# Modem.net
KiCad netlist of a schematic drawn in EAGLE
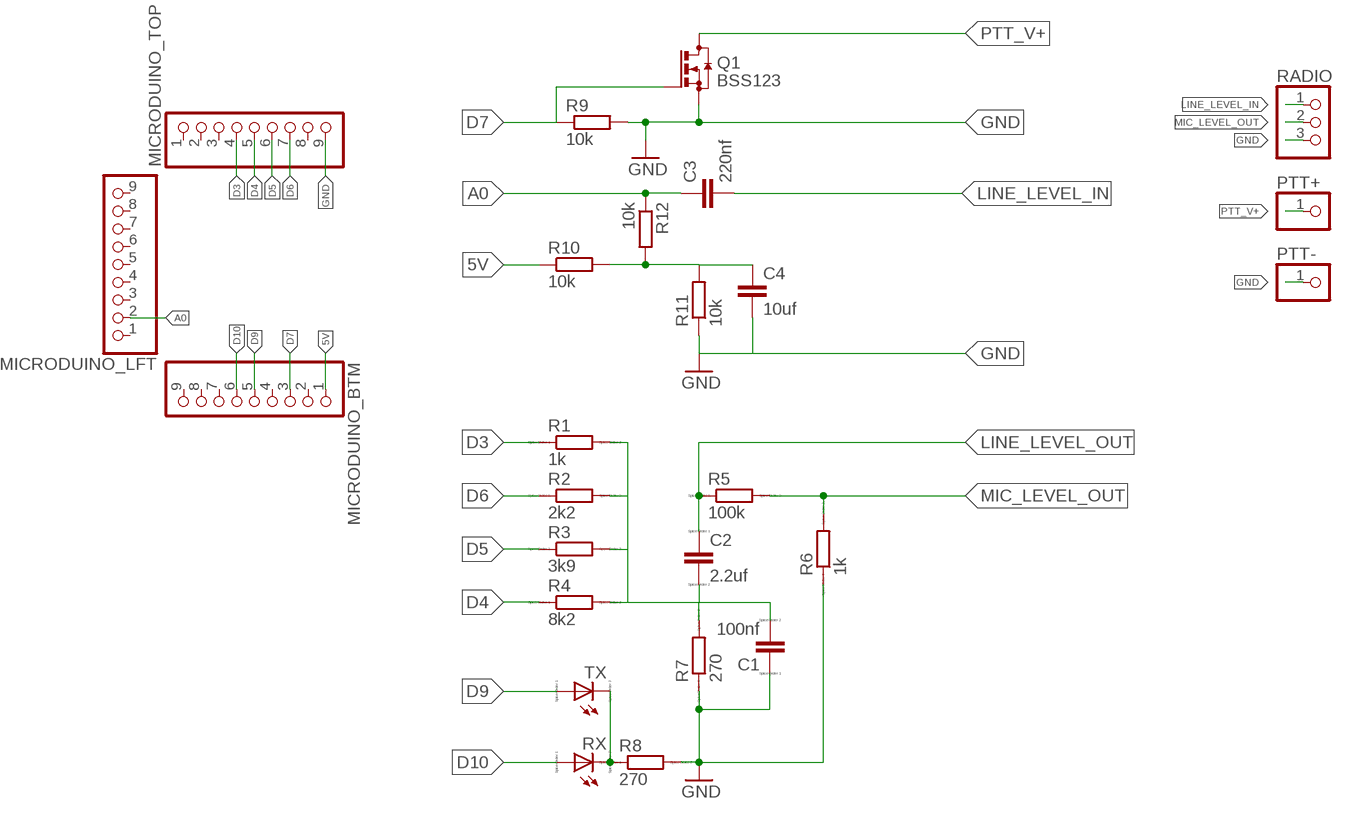
[diagram p0: schematic, sheet 1]

(export (version "E")
  (design (tool "Eeschema 10.0.6"))
  (components
    (comp (ref "C1")
      (value "100nf")
      (footprint "eagle-import:C0603")
      (libsource (lib "eagle-import") (part "CC0603"))
    )
    (comp (ref "C2")
      (value "2.2uf")
      (footprint "eagle-import:C1206")
      (libsource (lib "eagle-import") (part "CC1206"))
    )
    (comp (ref "C3")
      (value "220nf")
      (footprint "eagle-import:C0603")
      (libsource (lib "eagle-import") (part "C-EUC0603"))
    )
    (comp (ref "C4")
      (value "10uf")
      (footprint "eagle-import:C1206")
      (libsource (lib "eagle-import") (part "C-EUC1206"))
    )
    (comp (ref "MICRODUINO_BTM")
      (value "PINHD-1X9")
      (footprint "eagle-import:1X09-BIG")
      (libsource (lib "eagle-import") (part "PINHD-1X9"))
    )
    (comp (ref "MICRODUINO_LFT")
      (value "PINHD-1X9")
      (footprint "eagle-import:1X09-BIG")
      (libsource (lib "eagle-import") (part "PINHD-1X9"))
    )
    (comp (ref "MICRODUINO_TOP")
      (value "PINHD-1X9")
      (footprint "eagle-import:1X09-BIG")
      (libsource (lib "eagle-import") (part "PINHD-1X9"))
    )
    (comp (ref "PTT+")
      (value "PINHD-1X1")
      (footprint "eagle-import:1X01")
      (libsource (lib "eagle-import") (part "PINHD-1X1"))
    )
    (comp (ref "PTT-")
      (value "PINHD-1X1")
      (footprint "eagle-import:1X01")
      (libsource (lib "eagle-import") (part "PINHD-1X1"))
    )
    (comp (ref "Q1")
      (value "BSS123")
      (footprint "eagle-import:SOT23")
      (libsource (lib "eagle-import") (part "BSS123"))
    )
    (comp (ref "R1")
      (value "1k")
      (footprint "eagle-import:R0603")
      (libsource (lib "eagle-import") (part "resistor_R-EU_R0603"))
    )
    (comp (ref "R2")
      (value "2k2")
      (footprint "eagle-import:R0603")
      (libsource (lib "eagle-import") (part "resistor_R-EU_R0603"))
    )
    (comp (ref "R3")
      (value "3k9")
      (footprint "eagle-import:R0603")
      (libsource (lib "eagle-import") (part "resistor_R-EU_R0603"))
    )
    (comp (ref "R4")
      (value "8k2")
      (footprint "eagle-import:R0603")
      (libsource (lib "eagle-import") (part "resistor_R-EU_R0603"))
    )
    (comp (ref "R5")
      (value "100k")
      (footprint "eagle-import:R0603")
      (libsource (lib "eagle-import") (part "resistor_R-EU_R0603"))
    )
    (comp (ref "R6")
      (value "1k")
      (footprint "eagle-import:R0603")
      (libsource (lib "eagle-import") (part "resistor_R-EU_R0603"))
    )
    (comp (ref "R7")
      (value "270")
      (footprint "eagle-import:R0603")
      (libsource (lib "eagle-import") (part "resistor_R-EU_R0603"))
    )
    (comp (ref "R8")
      (value "270")
      (footprint "eagle-import:R0603")
      (libsource (lib "eagle-import") (part "resistor_R-EU_R0603"))
    )
    (comp (ref "R9")
      (value "10k")
      (footprint "eagle-import:R0603")
      (libsource (lib "eagle-import") (part "R-EU_R0603"))
    )
    (comp (ref "R10")
      (value "10k")
      (footprint "eagle-import:R0603")
      (libsource (lib "eagle-import") (part "R-EU_R0603"))
    )
    (comp (ref "R11")
      (value "10k")
      (footprint "eagle-import:R0603")
      (libsource (lib "eagle-import") (part "R-EU_R0603"))
    )
    (comp (ref "R12")
      (value "10k")
      (footprint "eagle-import:R0603")
      (libsource (lib "eagle-import") (part "R-EU_R0603"))
    )
    (comp (ref "RADIO")
      (value "PINHD-1X3")
      (footprint "eagle-import:1X03")
      (libsource (lib "eagle-import") (part "PINHD-1X3"))
    )
    (comp (ref "RX")
      (value "LED_E")
      (footprint "eagle-import:LED_1206")
      (libsource (lib "eagle-import") (part "LED_E"))
    )
    (comp (ref "TX")
      (value "LED_E")
      (footprint "eagle-import:LED_1206")
      (libsource (lib "eagle-import") (part "LED_E"))
    )
  )
  (nets
    (net (code "1") (name "5V") (class "Default")
      (node (ref "MICRODUINO_BTM") (pin "1") (pinfunction "1_1") (pintype "passive"))
      (node (ref "R10") (pin "1") (pinfunction "1_1") (pintype "passive"))
    )
    (net (code "2") (name "A0") (class "Default")
      (node (ref "C3") (pin "1") (pinfunction "1_1") (pintype "passive"))
      (node (ref "MICRODUINO_LFT") (pin "2") (pinfunction "2_2") (pintype "passive"))
      (node (ref "R12") (pin "1") (pinfunction "1_1") (pintype "passive"))
    )
    (net (code "3") (name "D3") (class "Default")
      (node (ref "MICRODUINO_TOP") (pin "4") (pinfunction "4_4") (pintype "passive"))
      (node (ref "R1") (pin "1") (pinfunction "1_1") (pintype "passive"))
    )
    (net (code "4") (name "D4") (class "Default")
      (node (ref "MICRODUINO_TOP") (pin "5") (pinfunction "5_5") (pintype "passive"))
      (node (ref "R4") (pin "1") (pinfunction "1_1") (pintype "passive"))
    )
    (net (code "5") (name "D5") (class "Default")
      (node (ref "MICRODUINO_TOP") (pin "6") (pinfunction "6_6") (pintype "passive"))
      (node (ref "R3") (pin "1") (pinfunction "1_1") (pintype "passive"))
    )
    (net (code "6") (name "D6") (class "Default")
      (node (ref "MICRODUINO_TOP") (pin "7") (pinfunction "7_7") (pintype "passive"))
      (node (ref "R2") (pin "1") (pinfunction "1_1") (pintype "passive"))
    )
    (net (code "7") (name "D7") (class "Default")
      (node (ref "MICRODUINO_BTM") (pin "3") (pinfunction "3_3") (pintype "passive"))
      (node (ref "Q1") (pin "1") (pinfunction "G_1") (pintype "passive"))
      (node (ref "R9") (pin "1") (pinfunction "1_1") (pintype "passive"))
    )
    (net (code "8") (name "D9") (class "Default")
      (node (ref "MICRODUINO_BTM") (pin "5") (pinfunction "5_5") (pintype "passive"))
      (node (ref "TX") (pin "A") (pinfunction "A_A") (pintype "passive"))
    )
    (net (code "9") (name "D10") (class "Default")
      (node (ref "MICRODUINO_BTM") (pin "6") (pinfunction "6_6") (pintype "passive"))
      (node (ref "RX") (pin "A") (pinfunction "A_A") (pintype "passive"))
    )
    (net (code "10") (name "GND") (class "Default")
      (node (ref "C1") (pin "1") (pinfunction "1_1") (pintype "passive"))
      (node (ref "C4") (pin "2") (pinfunction "2_2") (pintype "passive"))
      (node (ref "MICRODUINO_TOP") (pin "9") (pinfunction "9_9") (pintype "passive"))
      (node (ref "PTT-") (pin "1") (pinfunction "1_1") (pintype "passive"))
      (node (ref "Q1") (pin "2") (pinfunction "S_2") (pintype "passive"))
      (node (ref "R11") (pin "1") (pinfunction "1_1") (pintype "passive"))
      (node (ref "R6") (pin "1") (pinfunction "1_1") (pintype "passive"))
      (node (ref "R7") (pin "1") (pinfunction "1_1") (pintype "passive"))
      (node (ref "R8") (pin "2") (pinfunction "2_2") (pintype "passive"))
      (node (ref "R9") (pin "2") (pinfunction "2_2") (pintype "passive"))
      (node (ref "RADIO") (pin "3") (pinfunction "3_3") (pintype "passive"))
    )
    (net (code "11") (name "LINE_LEVEL_IN") (class "Default")
      (node (ref "C3") (pin "2") (pinfunction "2_2") (pintype "passive"))
      (node (ref "RADIO") (pin "1") (pinfunction "1_1") (pintype "passive"))
    )
    (net (code "12") (name "LINE_LEVEL_OUT") (class "Default")
      (node (ref "C2") (pin "1") (pinfunction "1_1") (pintype "passive"))
      (node (ref "R5") (pin "1") (pinfunction "1_1") (pintype "passive"))
    )
    (net (code "13") (name "MIC_LEVEL_OUT") (class "Default")
      (node (ref "R5") (pin "2") (pinfunction "2_2") (pintype "passive"))
      (node (ref "R6") (pin "2") (pinfunction "2_2") (pintype "passive"))
      (node (ref "RADIO") (pin "2") (pinfunction "2_2") (pintype "passive"))
    )
    (net (code "14") (name "Net-(C1-Pad2)") (class "Default")
      (node (ref "C1") (pin "2") (pinfunction "2_2") (pintype "passive"))
      (node (ref "C2") (pin "2") (pinfunction "2_2") (pintype "passive"))
      (node (ref "R1") (pin "2") (pinfunction "2_2") (pintype "passive"))
      (node (ref "R2") (pin "2") (pinfunction "2_2") (pintype "passive"))
      (node (ref "R3") (pin "2") (pinfunction "2_2") (pintype "passive"))
      (node (ref "R4") (pin "2") (pinfunction "2_2") (pintype "passive"))
      (node (ref "R7") (pin "2") (pinfunction "2_2") (pintype "passive"))
    )
    (net (code "15") (name "Net-(C4-Pad1)") (class "Default")
      (node (ref "C4") (pin "1") (pinfunction "1_1") (pintype "passive"))
      (node (ref "R10") (pin "2") (pinfunction "2_2") (pintype "passive"))
      (node (ref "R11") (pin "2") (pinfunction "2_2") (pintype "passive"))
      (node (ref "R12") (pin "2") (pinfunction "2_2") (pintype "passive"))
    )
    (net (code "16") (name "Net-(R8-Pad1)") (class "Default")
      (node (ref "R8") (pin "1") (pinfunction "1_1") (pintype "passive"))
      (node (ref "RX") (pin "C") (pinfunction "C_C") (pintype "passive"))
      (node (ref "TX") (pin "C") (pinfunction "C_C") (pintype "passive"))
    )
    (net (code "17") (name "PTT_V+") (class "Default")
      (node (ref "PTT+") (pin "1") (pinfunction "1_1") (pintype "passive"))
      (node (ref "Q1") (pin "3") (pinfunction "D_3") (pintype "passive"))
    )
    (net (code "18") (name "unconnected-(MICRODUINO_BTM-Pad2)") (class "Default")
      (node (ref "MICRODUINO_BTM") (pin "2") (pinfunction "2_2") (pintype "passive"))
    )
    (net (code "19") (name "unconnected-(MICRODUINO_BTM-Pad4)") (class "Default")
      (node (ref "MICRODUINO_BTM") (pin "4") (pinfunction "4_4") (pintype "passive"))
    )
    (net (code "20") (name "unconnected-(MICRODUINO_BTM-Pad7)") (class "Default")
      (node (ref "MICRODUINO_BTM") (pin "7") (pinfunction "7_7") (pintype "passive"))
    )
    (net (code "21") (name "unconnected-(MICRODUINO_BTM-Pad8)") (class "Default")
      (node (ref "MICRODUINO_BTM") (pin "8") (pinfunction "8_8") (pintype "passive"))
    )
    (net (code "22") (name "unconnected-(MICRODUINO_BTM-Pad9)") (class "Default")
      (node (ref "MICRODUINO_BTM") (pin "9") (pinfunction "9_9") (pintype "passive"))
    )
    (net (code "23") (name "unconnected-(MICRODUINO_LFT-Pad1)") (class "Default")
      (node (ref "MICRODUINO_LFT") (pin "1") (pinfunction "1_1") (pintype "passive"))
    )
    (net (code "24") (name "unconnected-(MICRODUINO_LFT-Pad3)") (class "Default")
      (node (ref "MICRODUINO_LFT") (pin "3") (pinfunction "3_3") (pintype "passive"))
    )
    (net (code "25") (name "unconnected-(MICRODUINO_LFT-Pad4)") (class "Default")
      (node (ref "MICRODUINO_LFT") (pin "4") (pinfunction "4_4") (pintype "passive"))
    )
    (net (code "26") (name "unconnected-(MICRODUINO_LFT-Pad5)") (class "Default")
      (node (ref "MICRODUINO_LFT") (pin "5") (pinfunction "5_5") (pintype "passive"))
    )
    (net (code "27") (name "unconnected-(MICRODUINO_LFT-Pad6)") (class "Default")
      (node (ref "MICRODUINO_LFT") (pin "6") (pinfunction "6_6") (pintype "passive"))
    )
    (net (code "28") (name "unconnected-(MICRODUINO_LFT-Pad7)") (class "Default")
      (node (ref "MICRODUINO_LFT") (pin "7") (pinfunction "7_7") (pintype "passive"))
    )
    (net (code "29") (name "unconnected-(MICRODUINO_LFT-Pad8)") (class "Default")
      (node (ref "MICRODUINO_LFT") (pin "8") (pinfunction "8_8") (pintype "passive"))
    )
    (net (code "30") (name "unconnected-(MICRODUINO_LFT-Pad9)") (class "Default")
      (node (ref "MICRODUINO_LFT") (pin "9") (pinfunction "9_9") (pintype "passive"))
    )
    (net (code "31") (name "unconnected-(MICRODUINO_TOP-Pad1)") (class "Default")
      (node (ref "MICRODUINO_TOP") (pin "1") (pinfunction "1_1") (pintype "passive"))
    )
    (net (code "32") (name "unconnected-(MICRODUINO_TOP-Pad2)") (class "Default")
      (node (ref "MICRODUINO_TOP") (pin "2") (pinfunction "2_2") (pintype "passive"))
    )
    (net (code "33") (name "unconnected-(MICRODUINO_TOP-Pad3)") (class "Default")
      (node (ref "MICRODUINO_TOP") (pin "3") (pinfunction "3_3") (pintype "passive"))
    )
    (net (code "34") (name "unconnected-(MICRODUINO_TOP-Pad8)") (class "Default")
      (node (ref "MICRODUINO_TOP") (pin "8") (pinfunction "8_8") (pintype "passive"))
    )
  )
)
